# Min_Sys.net
KiCad netlist of a schematic drawn in Altium Designer
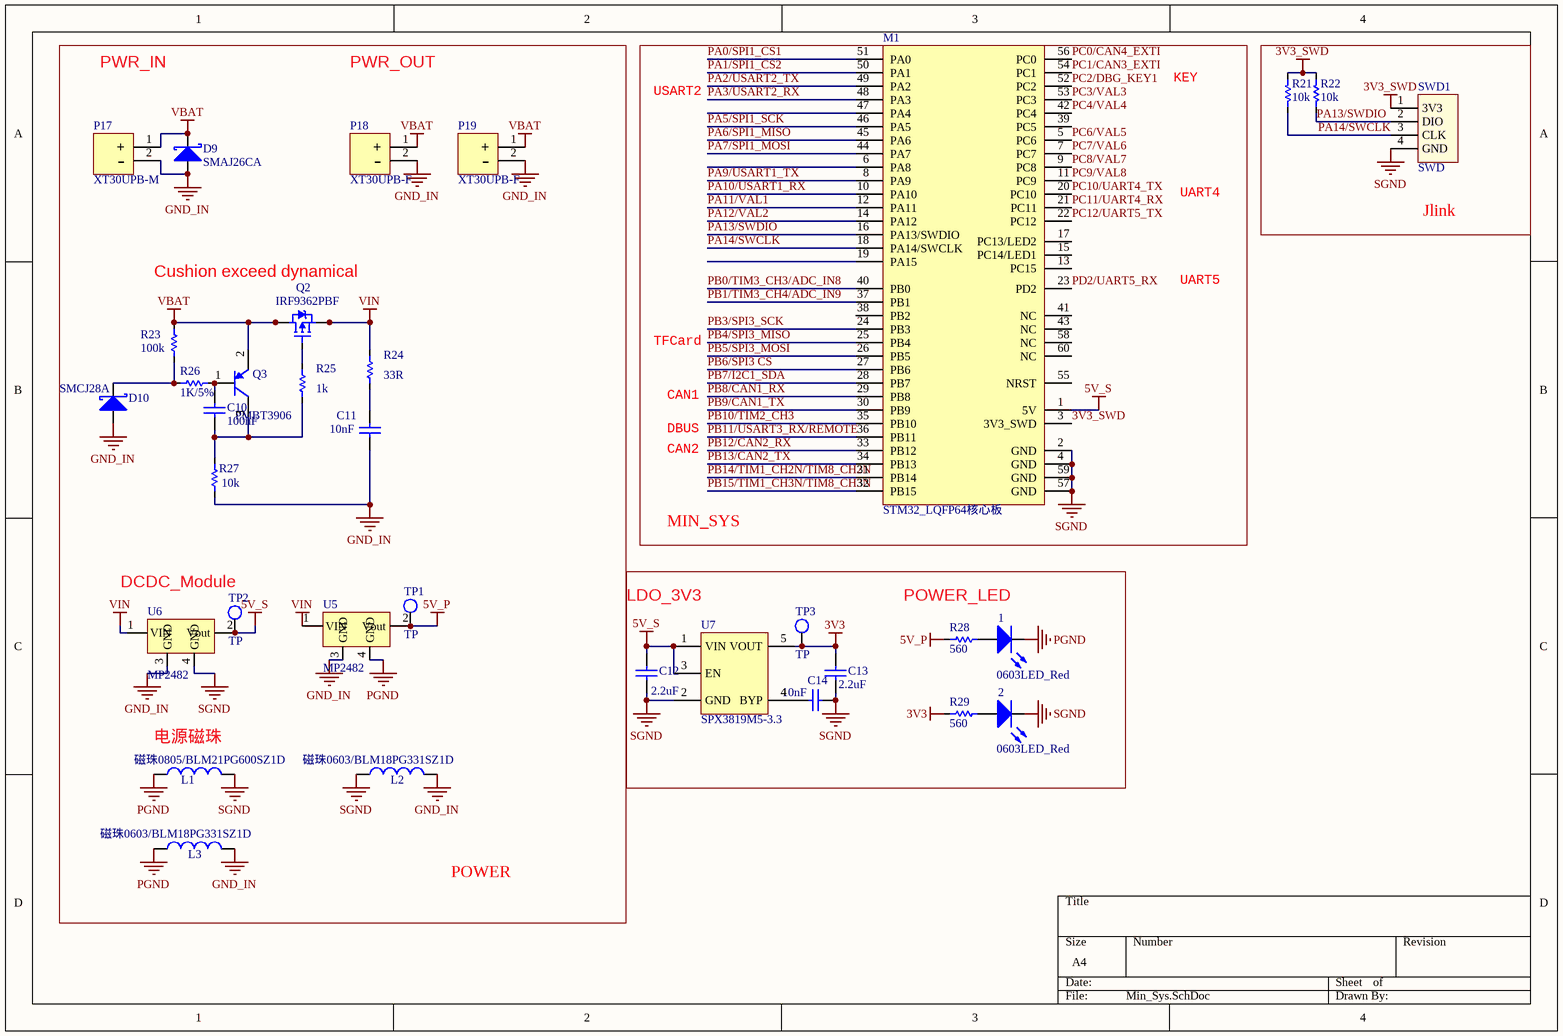
[diagram p0: Min_Sys.SchDoc]

(export (version "E")
  (design (tool "Eeschema 10.0.6"))
  (components
    (comp (ref "1")
      (value "0603LED_Red")
      (footprint "0603LED_R")
      (description "Typical RED, GREEN, YELLOW, AMBER GaAs LED")
      (fields (field (name "PUBLISHER") "Altium Limited"))
      (libsource (lib "MyComponents_v2.5") (part "LED"))
    )
    (comp (ref "2")
      (value "0603LED_Red")
      (footprint "0603LED_R")
      (description "Typical RED, GREEN, YELLOW, AMBER GaAs LED")
      (fields (field (name "PUBLISHER") "Altium Limited"))
      (libsource (lib "MyComponents_v2.5") (part "LED"))
    )
    (comp (ref "C10")
      (value "100nF")
      (footprint "0603C")
      (description "Capacitor")
      (fields (field (name "PUBLISHER") "Altium Limited"))
      (libsource (lib "") (part "Cap_1"))
    )
    (comp (ref "C11")
      (value "10nF")
      (footprint "0603C")
      (description "Capacitor")
      (fields (field (name "PUBLISHER") "Altium Limited"))
      (libsource (lib "") (part "Cap_1"))
    )
    (comp (ref "C12")
      (value "2.2uF")
      (footprint "0603C")
      (description "Capacitor")
      (fields (field (name "PUBLISHER") "Altium Limited"))
      (libsource (lib "MyComponents_v2.5") (part "Cap"))
    )
    (comp (ref "C13")
      (value "2.2uF")
      (footprint "0603C")
      (description "Capacitor")
      (fields (field (name "PUBLISHER") "Altium Limited"))
      (libsource (lib "MyComponents_v2.5") (part "Cap"))
    )
    (comp (ref "C14")
      (value "10nF")
      (footprint "0603C")
      (description "Capacitor")
      (fields (field (name "PUBLISHER") "Altium Limited"))
      (libsource (lib "MyComponents_v2.5") (part "Cap"))
    )
    (comp (ref "D9")
      (value "SMAJ26CA")
      (footprint "SMA/DO-214AC")
      (description "Schottky Diode")
      (fields (field (name "PUBLISHER") "Altium Limited"))
      (libsource (lib "MyComponents_v2.5") (part "D Schottky_SMAF"))
    )
    (comp (ref "D10")
      (value "SMCJ28A")
      (footprint "SMA/DO-214AC")
      (description "Schottky Diode")
      (fields (field (name "PUBLISHER") "Altium Limited"))
      (libsource (lib "MyComponents_v2.5") (part "D Schottky_SMAF"))
    )
    (comp (ref "L1")
      (value "磁珠0805/BLM21PG600SZ1D")
      (footprint "0805L")
      (description "Inductor")
      (fields (field (name "PUBLISHER") "Altium Limited"))
      (libsource (lib "MyComponents_v2.5") (part "Inductor"))
    )
    (comp (ref "L2")
      (value "磁珠0603/BLM18PG331SZ1D")
      (footprint "0603L")
      (description "Inductor")
      (fields (field (name "PUBLISHER") "Altium Limited"))
      (libsource (lib "MyComponents_v2.5") (part "Inductor"))
    )
    (comp (ref "L3")
      (value "磁珠0603/BLM18PG331SZ1D")
      (footprint "0603L")
      (description "Inductor")
      (fields (field (name "PUBLISHER") "Altium Limited"))
      (libsource (lib "MyComponents_v2.5") (part "Inductor"))
    )
    (comp (ref "M1")
      (value "STM32_LQFP64核心板")
      (footprint "STM32_LQFP64核心板")
      (description "STM32_LQFP64核心板\r\n兼容F105Rx、F405RGT6、F446Rx\r\n尺寸23mm x 25mm")
      (libsource (lib "MyComponents_v2.5") (part "STM32_LQFP64核心板"))
    )
    (comp (ref "P17")
      (value "XT30UPB-M")
      (footprint "XT30UPB-MALE")
      (libsource (lib "MyComponents_v2.5") (part "XT30/60/90"))
    )
    (comp (ref "P18")
      (value "XT30UPB-F")
      (footprint "XT30UPB-FEMALE")
      (libsource (lib "MyComponents_v2.5") (part "XT30/60/90"))
    )
    (comp (ref "P19")
      (value "XT30UPB-F")
      (footprint "XT30UPB-FEMALE")
      (libsource (lib "MyComponents_v2.5") (part "XT30/60/90"))
    )
    (comp (ref "Q2")
      (value "IRF9362PBF")
      (footprint "SON5X6")
      (description "P-Channel Power MOSFET")
      (fields (field (name "PUBLISHER") "Altium Limited"))
      (libsource (lib "MyComponents_v2.5") (part "PMOS"))
    )
    (comp (ref "Q3")
      (value "PMBT3906")
      (footprint "SOT-23-3")
      (description "PNP Bipolar Transistor")
      (fields (field (name "PUBLISHER") "Altium Limited"))
      (libsource (lib "MyComponents_v2.5") (part "PNP"))
    )
    (comp (ref "R21")
      (value "10k")
      (footprint "0603R")
      (description "Resistor")
      (fields (field (name "PUBLISHER") "Altium Limited"))
      (libsource (lib "MyComponents_v2.5") (part "Res1"))
    )
    (comp (ref "R22")
      (value "10k")
      (footprint "0603R")
      (description "Resistor")
      (fields (field (name "PUBLISHER") "Altium Limited"))
      (libsource (lib "MyComponents_v2.5") (part "Res1"))
    )
    (comp (ref "R23")
      (value "100k")
      (footprint "0603R")
      (description "Resistor")
      (fields (field (name "PUBLISHER") "Altium Limited"))
      (libsource (lib "") (part "Res1_1"))
    )
    (comp (ref "R24")
      (value "33R")
      (footprint "0603R")
      (description "Resistor")
      (fields (field (name "PUBLISHER") "Altium Limited"))
      (libsource (lib "") (part "Res1_1"))
    )
    (comp (ref "R25")
      (value "1k")
      (footprint "0603R")
      (description "Resistor")
      (fields (field (name "PUBLISHER") "Altium Limited"))
      (libsource (lib "") (part "Res1_1"))
    )
    (comp (ref "R26")
      (value "1K/5%")
      (footprint "0603R")
      (description "Resistor")
      (fields (field (name "PUBLISHER") "Altium Limited"))
      (libsource (lib "") (part "Res1_1"))
    )
    (comp (ref "R27")
      (value "10k")
      (footprint "0603R")
      (description "Resistor")
      (fields (field (name "PUBLISHER") "Altium Limited"))
      (libsource (lib "") (part "Res1_1"))
    )
    (comp (ref "R28")
      (value "560")
      (footprint "0603R")
      (description "Resistor")
      (fields (field (name "PUBLISHER") "Altium Limited"))
      (libsource (lib "MyComponents_v2.5") (part "Res1"))
    )
    (comp (ref "R29")
      (value "560")
      (footprint "0603R")
      (description "Resistor")
      (fields (field (name "PUBLISHER") "Altium Limited"))
      (libsource (lib "MyComponents_v2.5") (part "Res1"))
    )
    (comp (ref "SWD1")
      (value "SWD")
      (footprint "HEADER 4x1")
      (libsource (lib "MyComponents_v2.5") (part "SWD_HEADER"))
    )
    (comp (ref "TP1")
      (value "TP")
      (footprint "TP_VIA")
      (description "Test Point")
      (libsource (lib "MyComponents_v2.5") (part "TP"))
    )
    (comp (ref "TP2")
      (value "TP")
      (footprint "TP_VIA")
      (description "Test Point")
      (libsource (lib "MyComponents_v2.5") (part "TP"))
    )
    (comp (ref "TP3")
      (value "TP")
      (footprint "TP_VIA")
      (description "Test Point")
      (libsource (lib "MyComponents_v2.5") (part "TP"))
    )
    (comp (ref "U5")
      (value "MP2482")
      (footprint "MP2482_PowerModule")
      (libsource (lib "MyComponents_v2.5") (part "MP2482_PowerModule"))
    )
    (comp (ref "U6")
      (value "MP2482")
      (footprint "MP2482_PowerModule")
      (libsource (lib "MyComponents_v2.5") (part "MP2482_PowerModule"))
    )
    (comp (ref "U7")
      (value "SPX3819M5-3.3")
      (footprint "SOT-23-5 L")
      (libsource (lib "MyComponents_v2.5") (part "LDO_SOT23-5"))
    )
  )
  (nets
    (net (code "1") (name "/PA0{slash}SPI1_CS1") (class "Default")
      (node (ref "M1") (pin "51") (pinfunction "PA0_51") (pintype "passive"))
    )
    (net (code "2") (name "/PA1{slash}SPI1_CS2") (class "Default")
      (node (ref "M1") (pin "50") (pinfunction "PA1_50") (pintype "passive"))
    )
    (net (code "3") (name "/PA2{slash}USART2_TX") (class "Default")
      (node (ref "M1") (pin "49") (pinfunction "PA2_49") (pintype "passive"))
    )
    (net (code "4") (name "/PA3{slash}USART2_RX") (class "Default")
      (node (ref "M1") (pin "48") (pinfunction "PA3_48") (pintype "passive"))
    )
    (net (code "5") (name "/PA5{slash}SPI1_SCK") (class "Default")
      (node (ref "M1") (pin "46") (pinfunction "PA5_46") (pintype "passive"))
    )
    (net (code "6") (name "/PA6{slash}SPI1_MISO") (class "Default")
      (node (ref "M1") (pin "45") (pinfunction "PA6_45") (pintype "passive"))
    )
    (net (code "7") (name "/PA7{slash}SPI1_MOSI") (class "Default")
      (node (ref "M1") (pin "44") (pinfunction "PA7_44") (pintype "passive"))
    )
    (net (code "8") (name "/PA9{slash}USART1_TX") (class "Default")
      (node (ref "M1") (pin "8") (pinfunction "PA9_8") (pintype "passive"))
    )
    (net (code "9") (name "/PA10{slash}USART1_RX") (class "Default")
      (node (ref "M1") (pin "10") (pinfunction "PA10_10") (pintype "passive"))
    )
    (net (code "10") (name "/PA11{slash}VAL1") (class "Default")
      (node (ref "M1") (pin "12") (pinfunction "PA11_12") (pintype "passive"))
    )
    (net (code "11") (name "/PA12{slash}VAL2") (class "Default")
      (node (ref "M1") (pin "14") (pinfunction "PA12_14") (pintype "passive"))
    )
    (net (code "12") (name "/PA13{slash}SWDIO") (class "Default")
      (node (ref "M1") (pin "16") (pinfunction "PA13/SWDIO_16") (pintype "passive"))
      (node (ref "R22") (pin "1") (pinfunction "1_1") (pintype "passive"))
      (node (ref "SWD1") (pin "2") (pinfunction "DIO_2") (pintype "passive"))
    )
    (net (code "13") (name "/PA14{slash}SWCLK") (class "Default")
      (node (ref "M1") (pin "18") (pinfunction "PA14/SWCLK_18") (pintype "passive"))
      (node (ref "R21") (pin "1") (pinfunction "1_1") (pintype "passive"))
      (node (ref "SWD1") (pin "3") (pinfunction "CLK_3") (pintype "passive"))
    )
    (net (code "14") (name "/PB0{slash}TIM3_CH3{slash}ADC_IN8") (class "Default")
      (node (ref "M1") (pin "40") (pinfunction "PB0_40") (pintype "passive"))
    )
    (net (code "15") (name "/PB1{slash}TIM3_CH4{slash}ADC_IN9") (class "Default")
      (node (ref "M1") (pin "37") (pinfunction "PB1_37") (pintype "passive"))
    )
    (net (code "16") (name "/PB3{slash}SPI3_SCK") (class "Default")
      (node (ref "M1") (pin "24") (pinfunction "PB3_24") (pintype "passive"))
    )
    (net (code "17") (name "/PB4{slash}SPI3_MISO") (class "Default")
      (node (ref "M1") (pin "25") (pinfunction "PB4_25") (pintype "passive"))
    )
    (net (code "18") (name "/PB5{slash}SPI3_MOSI") (class "Default")
      (node (ref "M1") (pin "26") (pinfunction "PB5_26") (pintype "passive"))
    )
    (net (code "19") (name "/PB6{slash}SPI3 CS") (class "Default")
      (node (ref "M1") (pin "27") (pinfunction "PB6_27") (pintype "passive"))
    )
    (net (code "20") (name "/PB7{slash}I2C1_SDA") (class "Default")
      (node (ref "M1") (pin "28") (pinfunction "PB7_28") (pintype "passive"))
    )
    (net (code "21") (name "/PB8{slash}CAN1_RX") (class "Default")
      (node (ref "M1") (pin "29") (pinfunction "PB8_29") (pintype "passive"))
    )
    (net (code "22") (name "/PB9{slash}CAN1_TX") (class "Default")
      (node (ref "M1") (pin "30") (pinfunction "PB9_30") (pintype "passive"))
    )
    (net (code "23") (name "/PB10{slash}TIM2_CH3") (class "Default")
      (node (ref "M1") (pin "35") (pinfunction "PB10_35") (pintype "passive"))
    )
    (net (code "24") (name "/PB11{slash}USART3_RX{slash}REMOTE") (class "Default")
      (node (ref "M1") (pin "36") (pinfunction "PB11_36") (pintype "passive"))
    )
    (net (code "25") (name "/PB12{slash}CAN2_RX") (class "Default")
      (node (ref "M1") (pin "33") (pinfunction "PB12_33") (pintype "passive"))
    )
    (net (code "26") (name "/PB13{slash}CAN2_TX") (class "Default")
      (node (ref "M1") (pin "34") (pinfunction "PB13_34") (pintype "passive"))
    )
    (net (code "27") (name "/PB14{slash}TIM1_CH2N{slash}TIM8_CH2N") (class "Default")
      (node (ref "M1") (pin "31") (pinfunction "PB14_31") (pintype "passive"))
    )
    (net (code "28") (name "/PB15{slash}TIM1_CH3N{slash}TIM8_CH3N") (class "Default")
      (node (ref "M1") (pin "32") (pinfunction "PB15_32") (pintype "passive"))
    )
    (net (code "29") (name "/PC0{slash}CAN4_EXTI") (class "Default")
      (node (ref "M1") (pin "56") (pinfunction "PC0_56") (pintype "passive"))
    )
    (net (code "30") (name "/PC1{slash}CAN3_EXTI") (class "Default")
      (node (ref "M1") (pin "54") (pinfunction "PC1_54") (pintype "passive"))
    )
    (net (code "31") (name "/PC2{slash}DBG_KEY1") (class "Default")
      (node (ref "M1") (pin "52") (pinfunction "PC2_52") (pintype "passive"))
    )
    (net (code "32") (name "/PC3{slash}VAL3") (class "Default")
      (node (ref "M1") (pin "53") (pinfunction "PC3_53") (pintype "passive"))
    )
    (net (code "33") (name "/PC4{slash}VAL4") (class "Default")
      (node (ref "M1") (pin "42") (pinfunction "PC4_42") (pintype "passive"))
    )
    (net (code "34") (name "/PC6{slash}VAL5") (class "Default")
      (node (ref "M1") (pin "5") (pinfunction "PC6_5") (pintype "passive"))
    )
    (net (code "35") (name "/PC7{slash}VAL6") (class "Default")
      (node (ref "M1") (pin "7") (pinfunction "PC7_7") (pintype "passive"))
    )
    (net (code "36") (name "/PC8{slash}VAL7") (class "Default")
      (node (ref "M1") (pin "9") (pinfunction "PC8_9") (pintype "passive"))
    )
    (net (code "37") (name "/PC9{slash}VAL8") (class "Default")
      (node (ref "M1") (pin "11") (pinfunction "PC9_11") (pintype "passive"))
    )
    (net (code "38") (name "/PC10{slash}UART4_TX") (class "Default")
      (node (ref "M1") (pin "20") (pinfunction "PC10_20") (pintype "passive"))
    )
    (net (code "39") (name "/PC11{slash}UART4_RX") (class "Default")
      (node (ref "M1") (pin "21") (pinfunction "PC11_21") (pintype "passive"))
    )
    (net (code "40") (name "/PC12{slash}UART5_TX") (class "Default")
      (node (ref "M1") (pin "22") (pinfunction "PC12_22") (pintype "passive"))
    )
    (net (code "41") (name "/PD2{slash}UART5_RX") (class "Default")
      (node (ref "M1") (pin "23") (pinfunction "PD2_23") (pintype "passive"))
    )
    (net (code "42") (name "3V3") (class "Default")
      (node (ref "C13") (pin "1") (pinfunction "1_1") (pintype "passive"))
      (node (ref "R29") (pin "2") (pinfunction "2_2") (pintype "passive"))
      (node (ref "TP3") (pin "1") (pinfunction "TP_1") (pintype "open_collector"))
      (node (ref "U7") (pin "5") (pinfunction "VOUT_5") (pintype "passive"))
    )
    (net (code "43") (name "3V3_SWD") (class "Default")
      (node (ref "M1") (pin "3") (pinfunction "3V3_SWD_3") (pintype "passive"))
      (node (ref "R21") (pin "2") (pinfunction "2_2") (pintype "passive"))
      (node (ref "R22") (pin "2") (pinfunction "2_2") (pintype "passive"))
      (node (ref "SWD1") (pin "1") (pinfunction "3V3_1") (pintype "passive"))
    )
    (net (code "44") (name "5V_P") (class "Default")
      (node (ref "R28") (pin "2") (pinfunction "2_2") (pintype "passive"))
      (node (ref "TP1") (pin "1") (pinfunction "TP_1") (pintype "open_collector"))
      (node (ref "U5") (pin "2") (pinfunction "Vout_2") (pintype "passive"))
    )
    (net (code "45") (name "5V_S") (class "Default")
      (node (ref "C12") (pin "2") (pinfunction "2_2") (pintype "passive"))
      (node (ref "M1") (pin "1") (pinfunction "5V_1") (pintype "passive"))
      (node (ref "TP2") (pin "1") (pinfunction "TP_1") (pintype "open_collector"))
      (node (ref "U6") (pin "2") (pinfunction "Vout_2") (pintype "passive"))
      (node (ref "U7") (pin "1") (pinfunction "VIN_1") (pintype "passive"))
      (node (ref "U7") (pin "3") (pinfunction "EN_3") (pintype "passive"))
    )
    (net (code "46") (name "GND_IN") (class "Default")
      (node (ref "C11") (pin "1") (pinfunction "1_1") (pintype "passive"))
      (node (ref "D10") (pin "1") (pinfunction "1_1") (pintype "passive"))
      (node (ref "D9") (pin "1") (pinfunction "1_1") (pintype "passive"))
      (node (ref "L2") (pin "2") (pinfunction "2_2") (pintype "passive"))
      (node (ref "L3") (pin "2") (pinfunction "2_2") (pintype "passive"))
      (node (ref "P17") (pin "2") (pinfunction "-_2") (pintype "passive"))
      (node (ref "P18") (pin "2") (pinfunction "-_2") (pintype "passive"))
      (node (ref "P19") (pin "2") (pinfunction "-_2") (pintype "passive"))
      (node (ref "R27") (pin "2") (pinfunction "2_2") (pintype "passive"))
      (node (ref "U5") (pin "3") (pinfunction "GND_3") (pintype "passive"))
      (node (ref "U6") (pin "3") (pinfunction "GND_3") (pintype "passive"))
    )
    (net (code "47") (name "Net-(1-Pad1)") (class "Default")
      (node (ref "1") (pin "1") (pinfunction "1_1") (pintype "passive"))
      (node (ref "R28") (pin "1") (pinfunction "1_1") (pintype "passive"))
    )
    (net (code "48") (name "Net-(2-Pad1)") (class "Default")
      (node (ref "2") (pin "1") (pinfunction "1_1") (pintype "passive"))
      (node (ref "R29") (pin "1") (pinfunction "1_1") (pintype "passive"))
    )
    (net (code "49") (name "Net-(C11-Pad2)") (class "Default")
      (node (ref "C11") (pin "2") (pinfunction "2_2") (pintype "passive"))
      (node (ref "R24") (pin "2") (pinfunction "2_2") (pintype "passive"))
    )
    (net (code "50") (name "Net-(D10-Pad2)") (class "Default")
      (node (ref "D10") (pin "2") (pinfunction "2_2") (pintype "passive"))
      (node (ref "R23") (pin "2") (pinfunction "2_2") (pintype "passive"))
      (node (ref "R26") (pin "1") (pinfunction "1_1") (pintype "passive"))
    )
    (net (code "51") (name "Net-(Q2-G)") (class "Default")
      (node (ref "Q2") (pin "4") (pinfunction "G_4") (pintype "passive"))
      (node (ref "R25") (pin "1") (pinfunction "1_1") (pintype "passive"))
    )
    (net (code "52") (name "Net-(Q3-B)") (class "Default")
      (node (ref "C10") (pin "1") (pinfunction "1_1") (pintype "passive"))
      (node (ref "Q3") (pin "1") (pinfunction "B_1") (pintype "passive"))
      (node (ref "R26") (pin "2") (pinfunction "2_2") (pintype "passive"))
    )
    (net (code "53") (name "Net-(Q3-C)") (class "Default")
      (node (ref "C10") (pin "2") (pinfunction "2_2") (pintype "passive"))
      (node (ref "Q3") (pin "3") (pinfunction "C_3") (pintype "passive"))
      (node (ref "R25") (pin "2") (pinfunction "2_2") (pintype "passive"))
      (node (ref "R27") (pin "1") (pinfunction "1_1") (pintype "passive"))
    )
    (net (code "54") (name "Net-(U7-BYP)") (class "Default")
      (node (ref "C14") (pin "2") (pinfunction "2_2") (pintype "passive"))
      (node (ref "U7") (pin "4") (pinfunction "BYP_4") (pintype "passive"))
    )
    (net (code "55") (name "PGND") (class "Default")
      (node (ref "1") (pin "2") (pinfunction "2_2") (pintype "passive"))
      (node (ref "L1") (pin "1") (pinfunction "1_1") (pintype "passive"))
      (node (ref "L3") (pin "1") (pinfunction "1_1") (pintype "passive"))
      (node (ref "U5") (pin "4") (pinfunction "GND_4") (pintype "passive"))
    )
    (net (code "56") (name "SGND") (class "Default")
      (node (ref "2") (pin "2") (pinfunction "2_2") (pintype "passive"))
      (node (ref "C12") (pin "1") (pinfunction "1_1") (pintype "passive"))
      (node (ref "C13") (pin "2") (pinfunction "2_2") (pintype "passive"))
      (node (ref "C14") (pin "1") (pinfunction "1_1") (pintype "passive"))
      (node (ref "L1") (pin "2") (pinfunction "2_2") (pintype "passive"))
      (node (ref "L2") (pin "1") (pinfunction "1_1") (pintype "passive"))
      (node (ref "M1") (pin "2") (pinfunction "GND_2") (pintype "passive"))
      (node (ref "M1") (pin "4") (pinfunction "GND_4") (pintype "passive"))
      (node (ref "M1") (pin "57") (pinfunction "GND_57") (pintype "passive"))
      (node (ref "M1") (pin "59") (pinfunction "GND_59") (pintype "passive"))
      (node (ref "SWD1") (pin "4") (pinfunction "GND_4") (pintype "passive"))
      (node (ref "U6") (pin "4") (pinfunction "GND_4") (pintype "passive"))
      (node (ref "U7") (pin "2") (pinfunction "GND_2") (pintype "passive"))
    )
    (net (code "57") (name "VBAT") (class "Default")
      (node (ref "D9") (pin "2") (pinfunction "2_2") (pintype "passive"))
      (node (ref "P17") (pin "1") (pinfunction "+_1") (pintype "passive"))
      (node (ref "P18") (pin "1") (pinfunction "+_1") (pintype "passive"))
      (node (ref "P19") (pin "1") (pinfunction "+_1") (pintype "passive"))
      (node (ref "Q2") (pin "5") (pinfunction "D_5") (pintype "passive"))
      (node (ref "Q2") (pin "6") (pinfunction "D_6") (pintype "passive"))
      (node (ref "Q2") (pin "7") (pinfunction "D_7") (pintype "passive"))
      (node (ref "Q2") (pin "8") (pinfunction "D_8") (pintype "passive"))
      (node (ref "Q2") (pin "9") (pinfunction "D_9") (pintype "passive"))
      (node (ref "Q3") (pin "2") (pinfunction "E_2") (pintype "passive"))
      (node (ref "R23") (pin "1") (pinfunction "1_1") (pintype "passive"))
    )
    (net (code "58") (name "VIN") (class "Default")
      (node (ref "Q2") (pin "1") (pinfunction "S_1") (pintype "passive"))
      (node (ref "Q2") (pin "2") (pinfunction "S_2") (pintype "passive"))
      (node (ref "Q2") (pin "3") (pinfunction "S_3") (pintype "passive"))
      (node (ref "R24") (pin "1") (pinfunction "1_1") (pintype "passive"))
      (node (ref "U5") (pin "1") (pinfunction "VIN_1") (pintype "passive"))
      (node (ref "U6") (pin "1") (pinfunction "VIN_1") (pintype "passive"))
    )
    (net (code "59") (name "unconnected-(M1-NC-Pad41)") (class "Default")
      (node (ref "M1") (pin "41") (pinfunction "NC_41") (pintype "passive"))
    )
    (net (code "60") (name "unconnected-(M1-NC-Pad43)") (class "Default")
      (node (ref "M1") (pin "43") (pinfunction "NC_43") (pintype "passive"))
    )
    (net (code "61") (name "unconnected-(M1-NC-Pad58)") (class "Default")
      (node (ref "M1") (pin "58") (pinfunction "NC_58") (pintype "passive"))
    )
    (net (code "62") (name "unconnected-(M1-NC-Pad60)") (class "Default")
      (node (ref "M1") (pin "60") (pinfunction "NC_60") (pintype "passive"))
    )
    (net (code "63") (name "unconnected-(M1-NRST-Pad55)") (class "Default")
      (node (ref "M1") (pin "55") (pinfunction "NRST_55") (pintype "passive"))
    )
    (net (code "64") (name "unconnected-(M1-PA4-Pad47)") (class "Default")
      (node (ref "M1") (pin "47") (pinfunction "PA4_47") (pintype "passive"))
    )
    (net (code "65") (name "unconnected-(M1-PA8-Pad6)") (class "Default")
      (node (ref "M1") (pin "6") (pinfunction "PA8_6") (pintype "passive"))
    )
    (net (code "66") (name "unconnected-(M1-PA15-Pad19)") (class "Default")
      (node (ref "M1") (pin "19") (pinfunction "PA15_19") (pintype "passive"))
    )
    (net (code "67") (name "unconnected-(M1-PB2-Pad38)") (class "Default")
      (node (ref "M1") (pin "38") (pinfunction "PB2_38") (pintype "passive"))
    )
    (net (code "68") (name "unconnected-(M1-PC5-Pad39)") (class "Default")
      (node (ref "M1") (pin "39") (pinfunction "PC5_39") (pintype "passive"))
    )
    (net (code "69") (name "unconnected-(M1-PC13{slash}LED2-Pad17)") (class "Default")
      (node (ref "M1") (pin "17") (pinfunction "PC13/LED2_17") (pintype "passive"))
    )
    (net (code "70") (name "unconnected-(M1-PC14{slash}LED1-Pad15)") (class "Default")
      (node (ref "M1") (pin "15") (pinfunction "PC14/LED1_15") (pintype "passive"))
    )
    (net (code "71") (name "unconnected-(M1-PC15-Pad13)") (class "Default")
      (node (ref "M1") (pin "13") (pinfunction "PC15_13") (pintype "passive"))
    )
  )
)
